# jewellery.net
KiCad netlist of a schematic drawn in EAGLE
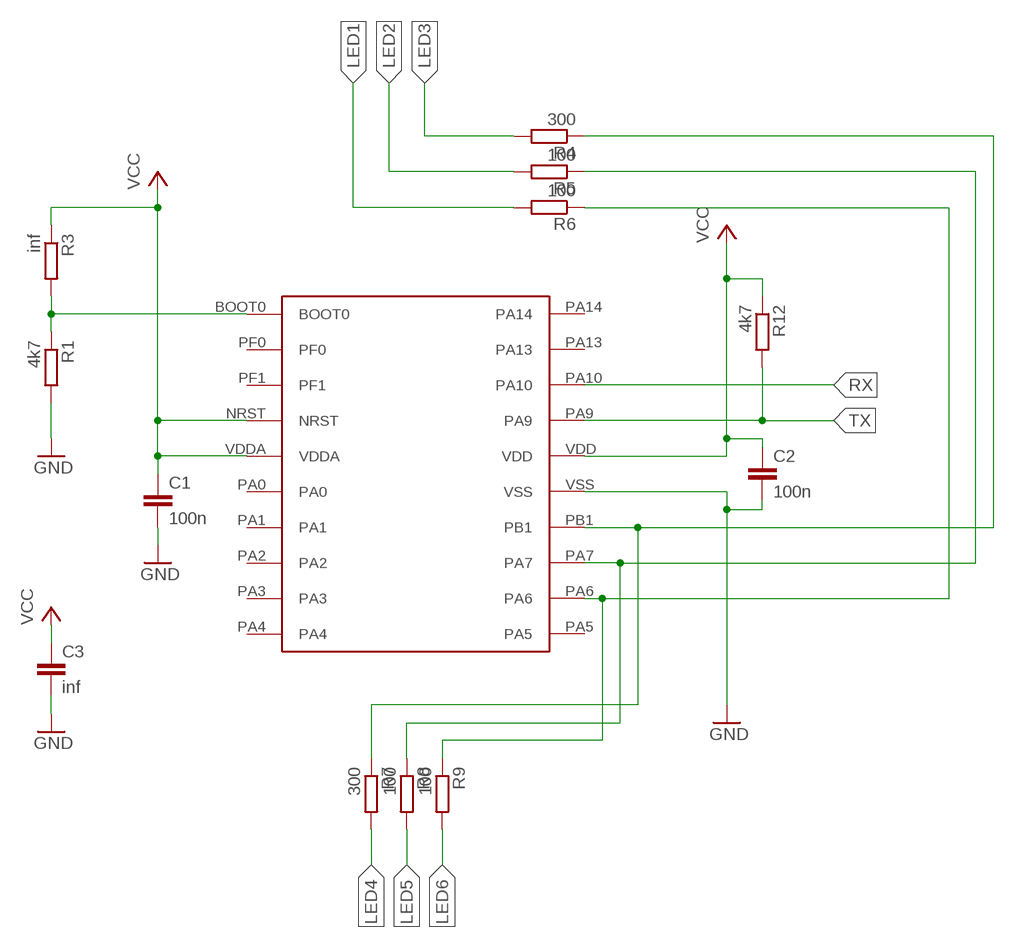
[diagram p0: schematic, sheet 1]

(export (version "E")
  (design (tool "Eeschema 10.0.6"))
  (components
    (comp (ref "C1")
      (value "100n")
      (footprint "eagle-import:C0805")
      (libsource (lib "eagle-import") (part "C-EUC0805"))
    )
    (comp (ref "C2")
      (value "100n")
      (footprint "eagle-import:C0805")
      (libsource (lib "eagle-import") (part "C-EUC0805"))
    )
    (comp (ref "C3")
      (value "inf")
      (footprint "eagle-import:C0805")
      (libsource (lib "eagle-import") (part "C-EUC0805"))
    )
    (comp (ref "R1")
      (value "4k7")
      (footprint "eagle-import:R0805")
      (libsource (lib "eagle-import") (part "R-EU_R0805"))
    )
    (comp (ref "R3")
      (value "inf")
      (footprint "eagle-import:R0805")
      (libsource (lib "eagle-import") (part "R-EU_R0805"))
    )
    (comp (ref "R4")
      (value "300")
      (footprint "eagle-import:R0805")
      (libsource (lib "eagle-import") (part "R-EU_R0805"))
    )
    (comp (ref "R5")
      (value "100")
      (footprint "eagle-import:R0805")
      (libsource (lib "eagle-import") (part "R-EU_R0805"))
    )
    (comp (ref "R6")
      (value "100")
      (footprint "eagle-import:R0805")
      (libsource (lib "eagle-import") (part "R-EU_R0805"))
    )
    (comp (ref "R7")
      (value "300")
      (footprint "eagle-import:R0805")
      (libsource (lib "eagle-import") (part "R-EU_R0805"))
    )
    (comp (ref "R8")
      (value "100")
      (footprint "eagle-import:R0805")
      (libsource (lib "eagle-import") (part "R-EU_R0805"))
    )
    (comp (ref "R9")
      (value "100")
      (footprint "eagle-import:R0805")
      (libsource (lib "eagle-import") (part "R-EU_R0805"))
    )
    (comp (ref "R12")
      (value "4k7")
      (footprint "eagle-import:R0805")
      (libsource (lib "eagle-import") (part "R-EU_R0805"))
    )
    (comp (ref "U$1")
      (value "STM32F0")
      (footprint "eagle-import:TSSOP20")
      (libsource (lib "eagle-import") (part "STM32F0"))
    )
  )
  (nets
    (net (code "1") (name "GND") (class "Default")
      (node (ref "C1") (pin "2") (pinfunction "2_2") (pintype "passive"))
      (node (ref "C2") (pin "2") (pinfunction "2_2") (pintype "passive"))
      (node (ref "C3") (pin "2") (pinfunction "2_2") (pintype "passive"))
      (node (ref "R1") (pin "2") (pinfunction "2_2") (pintype "passive"))
      (node (ref "U$1") (pin "VSS") (pinfunction "VSS_VSS") (pintype "bidirectional"))
    )
    (net (code "2") (name "LED1") (class "Default")
      (node (ref "R6") (pin "2") (pinfunction "2_2") (pintype "passive"))
    )
    (net (code "3") (name "LED2") (class "Default")
      (node (ref "R5") (pin "2") (pinfunction "2_2") (pintype "passive"))
    )
    (net (code "4") (name "LED3") (class "Default")
      (node (ref "R4") (pin "2") (pinfunction "2_2") (pintype "passive"))
    )
    (net (code "5") (name "LED4") (class "Default")
      (node (ref "R7") (pin "2") (pinfunction "2_2") (pintype "passive"))
    )
    (net (code "6") (name "LED5") (class "Default")
      (node (ref "R8") (pin "2") (pinfunction "2_2") (pintype "passive"))
    )
    (net (code "7") (name "LED6") (class "Default")
      (node (ref "R9") (pin "2") (pinfunction "2_2") (pintype "passive"))
    )
    (net (code "8") (name "Net-(R1-Pad1)") (class "Default")
      (node (ref "R1") (pin "1") (pinfunction "1_1") (pintype "passive"))
      (node (ref "R3") (pin "2") (pinfunction "2_2") (pintype "passive"))
      (node (ref "U$1") (pin "BOOT0") (pinfunction "BOOT0_BOOT0") (pintype "bidirectional"))
    )
    (net (code "9") (name "Net-(R4-Pad1)") (class "Default")
      (node (ref "R4") (pin "1") (pinfunction "1_1") (pintype "passive"))
      (node (ref "R7") (pin "1") (pinfunction "1_1") (pintype "passive"))
      (node (ref "U$1") (pin "PB1") (pinfunction "PB1_PB1") (pintype "bidirectional"))
    )
    (net (code "10") (name "Net-(R5-Pad1)") (class "Default")
      (node (ref "R5") (pin "1") (pinfunction "1_1") (pintype "passive"))
      (node (ref "R8") (pin "1") (pinfunction "1_1") (pintype "passive"))
      (node (ref "U$1") (pin "PA7") (pinfunction "PA7_PA7") (pintype "bidirectional"))
    )
    (net (code "11") (name "Net-(R6-Pad1)") (class "Default")
      (node (ref "R6") (pin "1") (pinfunction "1_1") (pintype "passive"))
      (node (ref "R9") (pin "1") (pinfunction "1_1") (pintype "passive"))
      (node (ref "U$1") (pin "PA6") (pinfunction "PA6_PA6") (pintype "bidirectional"))
    )
    (net (code "12") (name "RX") (class "Default")
      (node (ref "U$1") (pin "PA10") (pinfunction "PA10_PA10") (pintype "bidirectional"))
    )
    (net (code "13") (name "TX") (class "Default")
      (node (ref "R12") (pin "2") (pinfunction "2_2") (pintype "passive"))
      (node (ref "U$1") (pin "PA9") (pinfunction "PA9_PA9") (pintype "bidirectional"))
    )
    (net (code "14") (name "VCC") (class "Default")
      (node (ref "C1") (pin "1") (pinfunction "1_1") (pintype "passive"))
      (node (ref "C2") (pin "1") (pinfunction "1_1") (pintype "passive"))
      (node (ref "C3") (pin "1") (pinfunction "1_1") (pintype "passive"))
      (node (ref "R12") (pin "1") (pinfunction "1_1") (pintype "passive"))
      (node (ref "R3") (pin "1") (pinfunction "1_1") (pintype "passive"))
      (node (ref "U$1") (pin "NRST") (pinfunction "NRST_NRST") (pintype "bidirectional"))
      (node (ref "U$1") (pin "VDD") (pinfunction "VDD_VDD") (pintype "bidirectional"))
      (node (ref "U$1") (pin "VDDA") (pinfunction "VDDA_VDDA") (pintype "bidirectional"))
    )
    (net (code "15") (name "unconnected-(U$1-PadPA0)") (class "Default")
      (node (ref "U$1") (pin "PA0") (pinfunction "PA0_PA0") (pintype "bidirectional"))
    )
    (net (code "16") (name "unconnected-(U$1-PadPA1)") (class "Default")
      (node (ref "U$1") (pin "PA1") (pinfunction "PA1_PA1") (pintype "bidirectional"))
    )
    (net (code "17") (name "unconnected-(U$1-PadPA2)") (class "Default")
      (node (ref "U$1") (pin "PA2") (pinfunction "PA2_PA2") (pintype "bidirectional"))
    )
    (net (code "18") (name "unconnected-(U$1-PadPA3)") (class "Default")
      (node (ref "U$1") (pin "PA3") (pinfunction "PA3_PA3") (pintype "bidirectional"))
    )
    (net (code "19") (name "unconnected-(U$1-PadPA4)") (class "Default")
      (node (ref "U$1") (pin "PA4") (pinfunction "PA4_PA4") (pintype "bidirectional"))
    )
    (net (code "20") (name "unconnected-(U$1-PadPA5)") (class "Default")
      (node (ref "U$1") (pin "PA5") (pinfunction "PA5_PA5") (pintype "bidirectional"))
    )
    (net (code "21") (name "unconnected-(U$1-PadPA13)") (class "Default")
      (node (ref "U$1") (pin "PA13") (pinfunction "PA13_PA13") (pintype "bidirectional"))
    )
    (net (code "22") (name "unconnected-(U$1-PadPA14)") (class "Default")
      (node (ref "U$1") (pin "PA14") (pinfunction "PA14_PA14") (pintype "bidirectional"))
    )
    (net (code "23") (name "unconnected-(U$1-PadPF0)") (class "Default")
      (node (ref "U$1") (pin "PF0") (pinfunction "PF0_PF0") (pintype "bidirectional"))
    )
    (net (code "24") (name "unconnected-(U$1-PadPF1)") (class "Default")
      (node (ref "U$1") (pin "PF1") (pinfunction "PF1_PF1") (pintype "bidirectional"))
    )
  )
)
